# GDEnvSensorNode_Programmer.net
KiCad netlist of a schematic drawn in EAGLE
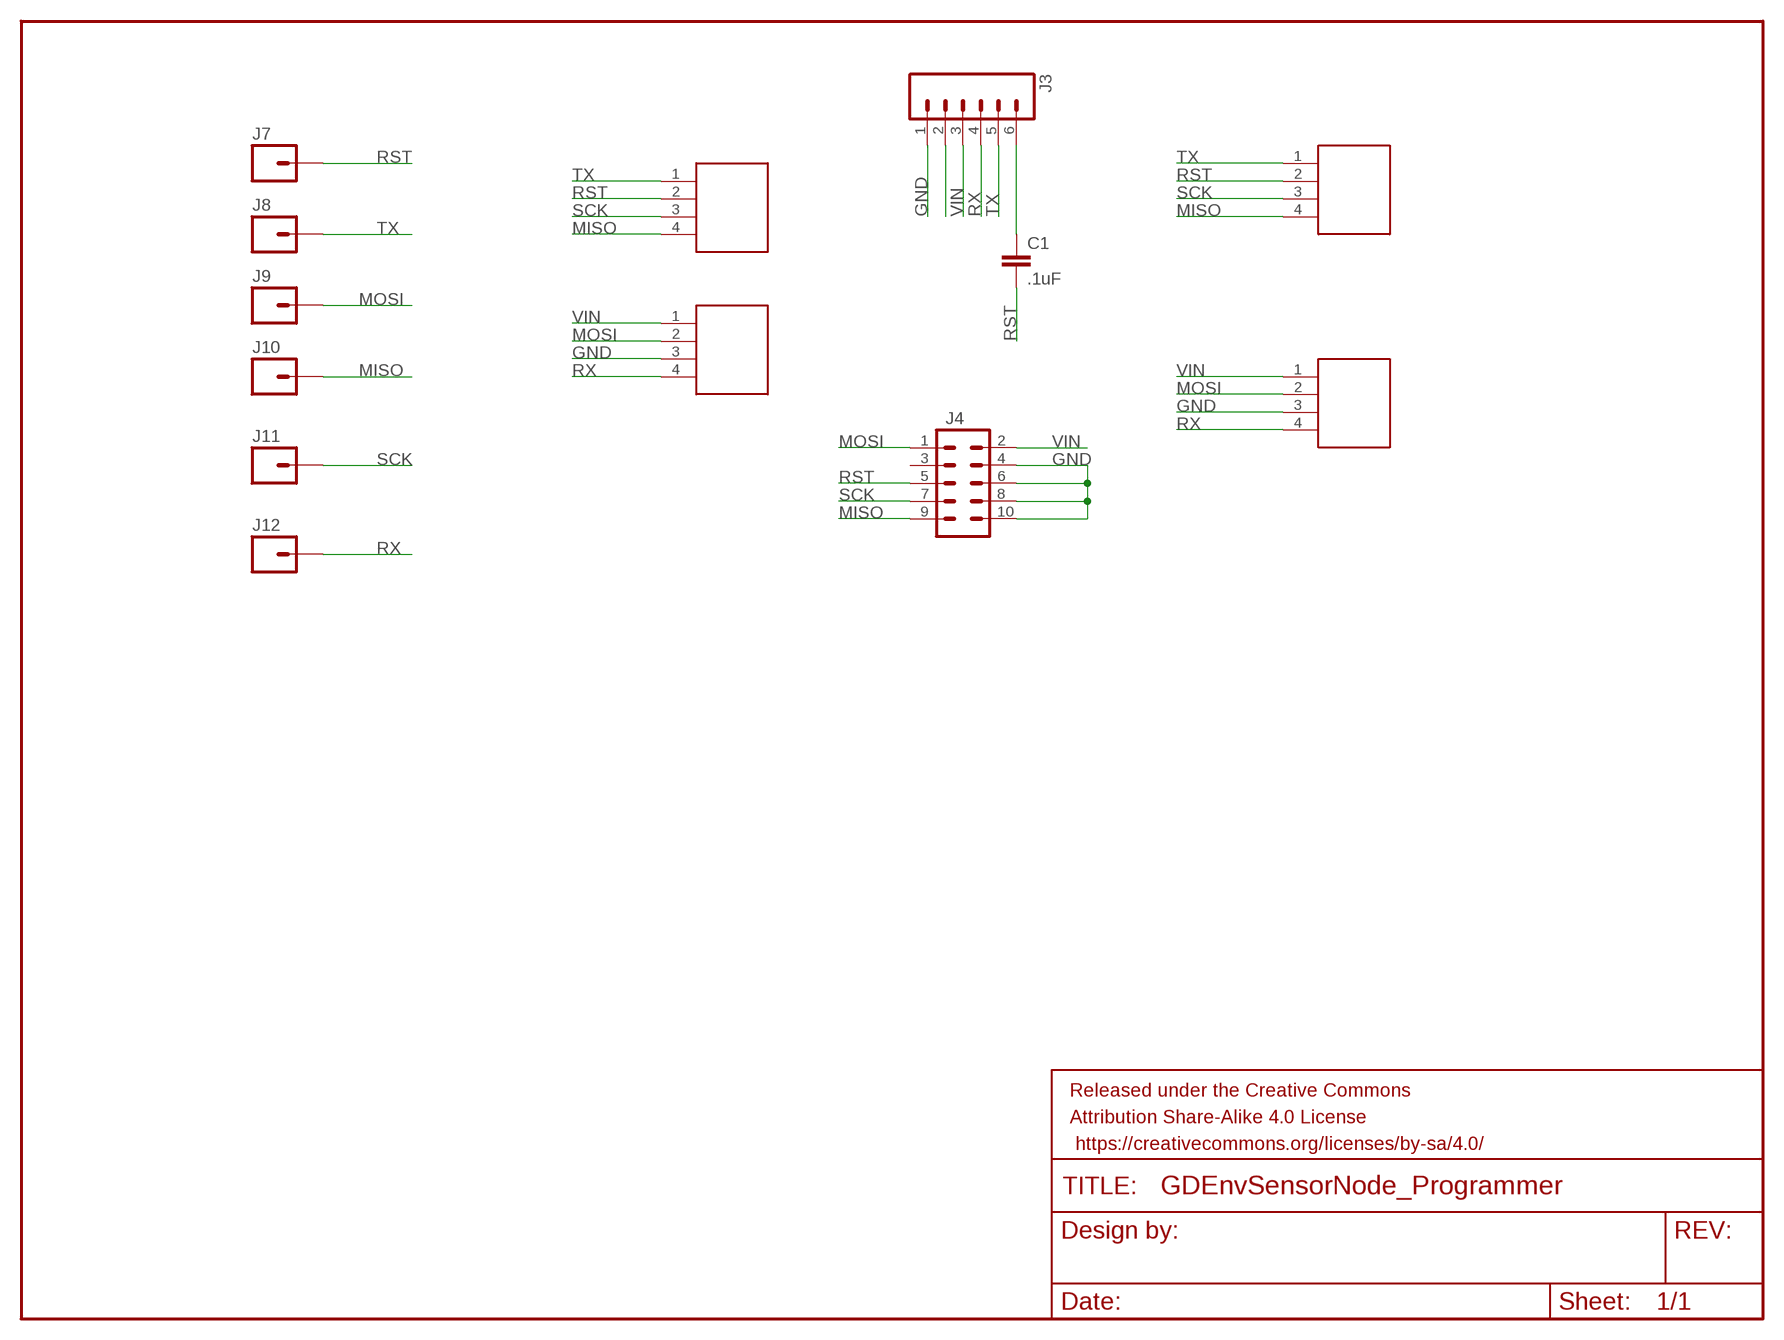
[diagram p0: schematic, sheet 1]

(export (version "E")
  (design (tool "Eeschema 10.0.6"))
  (components
    (comp (ref "C1")
      (value ".1uF")
      (footprint "eagle-import:0805")
      (libsource (lib "eagle-import") (part "CAP0805"))
    )
    (comp (ref "FRAME1")
      (value "FRAME-LETTER")
      (footprint "eagle-import:CREATIVE_COMMONS")
      (libsource (lib "eagle-import") (part "FRAME-LETTER"))
    )
    (comp (ref "J1")
      (value "4X.1IN_POGO_PIN")
      (footprint "eagle-import:4X.1IN_POGO_PIN")
      (libsource (lib "eagle-import") (part "4X.1IN_POGO_PIN"))
    )
    (comp (ref "J2")
      (value "4X.1IN_POGO_PIN")
      (footprint "eagle-import:4X.1IN_POGO_PIN")
      (libsource (lib "eagle-import") (part "4X.1IN_POGO_PIN"))
    )
    (comp (ref "J3")
      (value "M06LONGPADS")
      (footprint "eagle-import:1X06_LONGPADS")
      (libsource (lib "eagle-import") (part "M06LONGPADS"))
    )
    (comp (ref "J4")
      (value "M05X2PTH")
      (footprint "eagle-import:AVR_ICSP")
      (libsource (lib "eagle-import") (part "M05X2PTH"))
    )
    (comp (ref "J5")
      (value "4X.1IN_POGO_PIN")
      (footprint "eagle-import:4X.1IN_POGO_PIN")
      (libsource (lib "eagle-import") (part "4X.1IN_POGO_PIN"))
    )
    (comp (ref "J6")
      (value "4X.1IN_POGO_PIN")
      (footprint "eagle-import:4X.1IN_POGO_PIN")
      (libsource (lib "eagle-import") (part "4X.1IN_POGO_PIN"))
    )
    (comp (ref "J7")
      (value "M01PTH")
      (footprint "eagle-import:1X01")
      (libsource (lib "eagle-import") (part "M01PTH"))
    )
    (comp (ref "J8")
      (value "M01PTH")
      (footprint "eagle-import:1X01")
      (libsource (lib "eagle-import") (part "M01PTH"))
    )
    (comp (ref "J9")
      (value "M01PTH")
      (footprint "eagle-import:1X01")
      (libsource (lib "eagle-import") (part "M01PTH"))
    )
    (comp (ref "J10")
      (value "M01PTH")
      (footprint "eagle-import:1X01")
      (libsource (lib "eagle-import") (part "M01PTH"))
    )
    (comp (ref "J11")
      (value "M01PTH")
      (footprint "eagle-import:1X01")
      (libsource (lib "eagle-import") (part "M01PTH"))
    )
    (comp (ref "J12")
      (value "M01PTH")
      (footprint "eagle-import:1X01")
      (libsource (lib "eagle-import") (part "M01PTH"))
    )
  )
  (nets
    (net (code "1") (name "/GND") (class "Default")
      (node (ref "J2") (pin "3") (pinfunction "3_3") (pintype "bidirectional"))
      (node (ref "J3") (pin "1") (pinfunction "1_1") (pintype "passive"))
      (node (ref "J4") (pin "10") (pinfunction "10_10") (pintype "passive"))
      (node (ref "J4") (pin "4") (pinfunction "4_4") (pintype "passive"))
      (node (ref "J4") (pin "6") (pinfunction "6_6") (pintype "passive"))
      (node (ref "J4") (pin "8") (pinfunction "8_8") (pintype "passive"))
      (node (ref "J6") (pin "3") (pinfunction "3_3") (pintype "bidirectional"))
    )
    (net (code "2") (name "/MISO") (class "Default")
      (node (ref "J1") (pin "4") (pinfunction "4_4") (pintype "bidirectional"))
      (node (ref "J10") (pin "1") (pinfunction "1_1") (pintype "passive"))
      (node (ref "J4") (pin "9") (pinfunction "9_9") (pintype "passive"))
      (node (ref "J5") (pin "4") (pinfunction "4_4") (pintype "bidirectional"))
    )
    (net (code "3") (name "/MOSI") (class "Default")
      (node (ref "J2") (pin "2") (pinfunction "2_2") (pintype "bidirectional"))
      (node (ref "J4") (pin "1") (pinfunction "1_1") (pintype "passive"))
      (node (ref "J6") (pin "2") (pinfunction "2_2") (pintype "bidirectional"))
      (node (ref "J9") (pin "1") (pinfunction "1_1") (pintype "passive"))
    )
    (net (code "4") (name "/RST") (class "Default")
      (node (ref "C1") (pin "2") (pinfunction "2_2") (pintype "passive"))
      (node (ref "J1") (pin "2") (pinfunction "2_2") (pintype "bidirectional"))
      (node (ref "J4") (pin "5") (pinfunction "5_5") (pintype "passive"))
      (node (ref "J5") (pin "2") (pinfunction "2_2") (pintype "bidirectional"))
      (node (ref "J7") (pin "1") (pinfunction "1_1") (pintype "passive"))
    )
    (net (code "5") (name "/RX") (class "Default")
      (node (ref "J12") (pin "1") (pinfunction "1_1") (pintype "passive"))
      (node (ref "J2") (pin "4") (pinfunction "4_4") (pintype "bidirectional"))
      (node (ref "J3") (pin "4") (pinfunction "4_4") (pintype "passive"))
      (node (ref "J6") (pin "4") (pinfunction "4_4") (pintype "bidirectional"))
    )
    (net (code "6") (name "/SCK") (class "Default")
      (node (ref "J1") (pin "3") (pinfunction "3_3") (pintype "bidirectional"))
      (node (ref "J11") (pin "1") (pinfunction "1_1") (pintype "passive"))
      (node (ref "J4") (pin "7") (pinfunction "7_7") (pintype "passive"))
      (node (ref "J5") (pin "3") (pinfunction "3_3") (pintype "bidirectional"))
    )
    (net (code "7") (name "/TX") (class "Default")
      (node (ref "J1") (pin "1") (pinfunction "1_1") (pintype "bidirectional"))
      (node (ref "J3") (pin "5") (pinfunction "5_5") (pintype "passive"))
      (node (ref "J5") (pin "1") (pinfunction "1_1") (pintype "bidirectional"))
      (node (ref "J8") (pin "1") (pinfunction "1_1") (pintype "passive"))
    )
    (net (code "8") (name "/VIN") (class "Default")
      (node (ref "J2") (pin "1") (pinfunction "1_1") (pintype "bidirectional"))
      (node (ref "J3") (pin "3") (pinfunction "3_3") (pintype "passive"))
      (node (ref "J4") (pin "2") (pinfunction "2_2") (pintype "passive"))
      (node (ref "J6") (pin "1") (pinfunction "1_1") (pintype "bidirectional"))
    )
    (net (code "9") (name "Net-(C1-Pad1)") (class "Default")
      (node (ref "C1") (pin "1") (pinfunction "1_1") (pintype "passive"))
      (node (ref "J3") (pin "6") (pinfunction "6_6") (pintype "passive"))
    )
    (net (code "10") (name "unconnected-(J3-Pad2)") (class "Default")
      (node (ref "J3") (pin "2") (pinfunction "2_2") (pintype "passive"))
    )
    (net (code "11") (name "unconnected-(J4-Pad3)") (class "Default")
      (node (ref "J4") (pin "3") (pinfunction "3_3") (pintype "passive"))
    )
  )
)
